# Controller-Modul_1.net
KiCad netlist of a schematic drawn in EAGLE
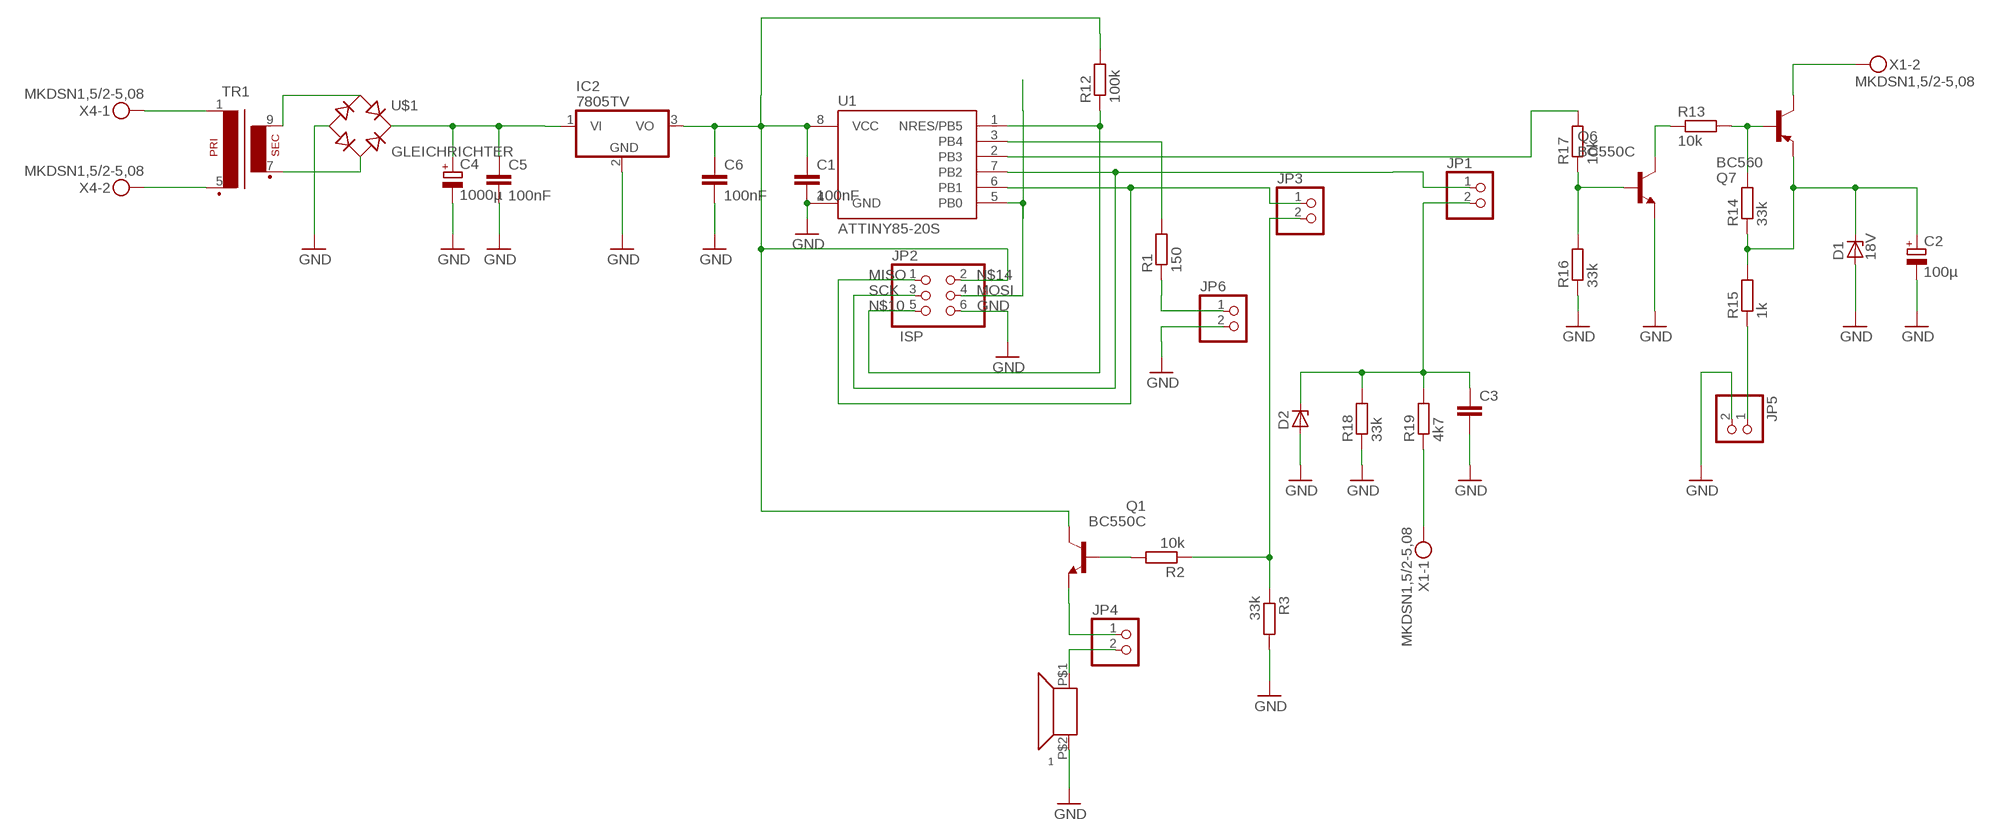
[diagram p0: schematic, sheet 1]

(export (version "E")
  (design (tool "Eeschema 10.0.6"))
  (components
    (comp (ref "1")
      (value "SUMMER4")
      (footprint "eagle-import:PIEZO-INDIKATOR-KPMG")
      (libsource (lib "eagle-import") (part "SUMMER4"))
    )
    (comp (ref "C1")
      (value "100nF")
      (footprint "eagle-import:C0805")
      (libsource (lib "eagle-import") (part "C-EUC0805"))
    )
    (comp (ref "C2")
      (value "100µ")
      (footprint "eagle-import:E2,5-7")
      (libsource (lib "eagle-import") (part "resistor_CPOL-EUE2.5-7"))
    )
    (comp (ref "C3")
      (value "C-EUC0603K")
      (footprint "eagle-import:C0603K")
      (libsource (lib "eagle-import") (part "C-EUC0603K"))
    )
    (comp (ref "C4")
      (value "1000µ")
      (footprint "eagle-import:E3,5-8")
      (libsource (lib "eagle-import") (part "CPOL-EUE3.5-8"))
    )
    (comp (ref "C5")
      (value "100nF")
      (footprint "eagle-import:C0805")
      (libsource (lib "eagle-import") (part "C-EUC0805"))
    )
    (comp (ref "C6")
      (value "100nF")
      (footprint "eagle-import:C0805")
      (libsource (lib "eagle-import") (part "C-EUC0805"))
    )
    (comp (ref "D1")
      (value "18V")
      (footprint "eagle-import:SOD80C")
      (libsource (lib "eagle-import") (part "ZENER-DIODESOD80C"))
    )
    (comp (ref "D2")
      (value "ZENER-DIODESOT23")
      (footprint "eagle-import:SOT23")
      (libsource (lib "eagle-import") (part "ZENER-DIODESOT23"))
    )
    (comp (ref "IC2")
      (value "7805TV")
      (footprint "eagle-import:TO220V")
      (libsource (lib "eagle-import") (part "78TV05"))
    )
    (comp (ref "JP1")
      (value "PINHD-1X2")
      (footprint "eagle-import:1X02")
      (libsource (lib "eagle-import") (part "PINHD-1X2"))
    )
    (comp (ref "JP2")
      (value "PINHD-2X3")
      (footprint "eagle-import:2X03")
      (libsource (lib "eagle-import") (part "PINHD-2X3"))
    )
    (comp (ref "JP3")
      (value "PINHD-1X2")
      (footprint "eagle-import:1X02")
      (libsource (lib "eagle-import") (part "PINHD-1X2"))
    )
    (comp (ref "JP4")
      (value "PINHD-1X2")
      (footprint "eagle-import:1X02")
      (libsource (lib "eagle-import") (part "PINHD-1X2"))
    )
    (comp (ref "JP5")
      (value "PINHD-1X2")
      (footprint "eagle-import:1X02")
      (libsource (lib "eagle-import") (part "PINHD-1X2"))
    )
    (comp (ref "JP6")
      (value "PINHD-1X2")
      (footprint "eagle-import:1X02")
      (libsource (lib "eagle-import") (part "PINHD-1X2"))
    )
    (comp (ref "Q1")
      (value "BC550C")
      (footprint "eagle-import:TO92-EBC")
      (libsource (lib "eagle-import") (part "BC550C"))
    )
    (comp (ref "Q6")
      (value "BC550C")
      (footprint "eagle-import:TO92-EBC")
      (libsource (lib "eagle-import") (part "BC550C"))
    )
    (comp (ref "Q7")
      (value "BC560")
      (footprint "eagle-import:TO92-EBC")
      (libsource (lib "eagle-import") (part "BC560"))
    )
    (comp (ref "R1")
      (value "150")
      (footprint "eagle-import:R1206")
      (libsource (lib "eagle-import") (part "R-EU_R1206"))
    )
    (comp (ref "R2")
      (value "10k")
      (footprint "eagle-import:R1206")
      (libsource (lib "eagle-import") (part "resistor_R-EU_R1206"))
    )
    (comp (ref "R3")
      (value "33k")
      (footprint "eagle-import:R1206")
      (libsource (lib "eagle-import") (part "resistor_R-EU_R1206"))
    )
    (comp (ref "R12")
      (value "100k")
      (footprint "eagle-import:R1206")
      (libsource (lib "eagle-import") (part "R-EU_R1206"))
    )
    (comp (ref "R13")
      (value "10k")
      (footprint "eagle-import:R1206")
      (libsource (lib "eagle-import") (part "resistor_R-EU_R1206"))
    )
    (comp (ref "R14")
      (value "33k")
      (footprint "eagle-import:R1206")
      (libsource (lib "eagle-import") (part "resistor_R-EU_R1206"))
    )
    (comp (ref "R15")
      (value "1k")
      (footprint "eagle-import:R1206")
      (libsource (lib "eagle-import") (part "resistor_R-EU_R1206"))
    )
    (comp (ref "R16")
      (value "33k")
      (footprint "eagle-import:R1206")
      (libsource (lib "eagle-import") (part "resistor_R-EU_R1206"))
    )
    (comp (ref "R17")
      (value "10k")
      (footprint "eagle-import:R1206")
      (libsource (lib "eagle-import") (part "resistor_R-EU_R1206"))
    )
    (comp (ref "R18")
      (value "33k")
      (footprint "eagle-import:R1206")
      (libsource (lib "eagle-import") (part "resistor_R-EU_R1206"))
    )
    (comp (ref "R19")
      (value "4k7")
      (footprint "eagle-import:R1206")
      (libsource (lib "eagle-import") (part "resistor_R-EU_R1206"))
    )
    (comp (ref "TR1")
      (value "EI38-1")
      (footprint "eagle-import:EI38-1")
      (libsource (lib "eagle-import") (part "EI38-1"))
    )
    (comp (ref "U$1")
      (value "GLEICHRICHTER")
      (footprint "eagle-import:KBPC1")
      (libsource (lib "eagle-import") (part "GLEICHRICHTER"))
    )
    (comp (ref "U1")
      (value "ATTINY85-20S")
      (footprint "eagle-import:SOIC8_EIAJ_208MIL")
      (libsource (lib "eagle-import") (part "ATTINY85S-20"))
    )
    (comp (ref "X1")
      (value "MKDSN1,5/2-5,08")
      (footprint "eagle-import:MKDSN1,5_2-5,08")
      (libsource (lib "eagle-import") (part "MKDSN1,5/2-5,08"))
    )
    (comp (ref "X4")
      (value "MKDSN1,5/2-5,08")
      (footprint "eagle-import:MKDSN1,5_2-5,08")
      (libsource (lib "eagle-import") (part "MKDSN1,5/2-5,08"))
    )
  )
  (nets
    (net (code "1") (name "/MISO") (class "Default")
      (node (ref "JP2") (pin "1") (pinfunction "1_1") (pintype "passive"))
      (node (ref "JP3") (pin "1") (pinfunction "1_1") (pintype "passive"))
      (node (ref "U1") (pin "6") (pinfunction "PB1_6") (pintype "bidirectional"))
    )
    (net (code "2") (name "/MOSI") (class "Default")
      (node (ref "JP2") (pin "4") (pinfunction "4_4") (pintype "passive"))
      (node (ref "U1") (pin "5") (pinfunction "PB0_5") (pintype "bidirectional"))
    )
    (net (code "3") (name "/N$10") (class "Default")
      (node (ref "JP2") (pin "5") (pinfunction "5_5") (pintype "passive"))
      (node (ref "R12") (pin "1") (pinfunction "1_1") (pintype "passive"))
      (node (ref "U1") (pin "1") (pinfunction "NRES/PB5_1") (pintype "bidirectional"))
    )
    (net (code "4") (name "/N$14") (class "Default")
      (node (ref "C1") (pin "1") (pinfunction "1_1") (pintype "passive"))
      (node (ref "C6") (pin "1") (pinfunction "1_1") (pintype "passive"))
      (node (ref "IC2") (pin "3") (pinfunction "VO_3") (pintype "passive"))
      (node (ref "JP2") (pin "2") (pinfunction "2_2") (pintype "passive"))
      (node (ref "Q1") (pin "C") (pinfunction "C_C") (pintype "passive"))
      (node (ref "R12") (pin "2") (pinfunction "2_2") (pintype "passive"))
      (node (ref "U1") (pin "8") (pinfunction "VCC_8") (pintype "power_in"))
    )
    (net (code "5") (name "/SCK") (class "Default")
      (node (ref "JP1") (pin "1") (pinfunction "1_1") (pintype "passive"))
      (node (ref "JP2") (pin "3") (pinfunction "3_3") (pintype "passive"))
      (node (ref "U1") (pin "7") (pinfunction "PB2_7") (pintype "bidirectional"))
    )
    (net (code "6") (name "GND") (class "Default")
      (node (ref "1") (pin "P$2") (pinfunction "+_P$2") (pintype "passive"))
      (node (ref "C1") (pin "2") (pinfunction "2_2") (pintype "passive"))
      (node (ref "C2") (pin "-") (pinfunction "-_-") (pintype "passive"))
      (node (ref "C3") (pin "2") (pinfunction "2_2") (pintype "passive"))
      (node (ref "C4") (pin "-") (pinfunction "-_-") (pintype "passive"))
      (node (ref "C5") (pin "2") (pinfunction "2_2") (pintype "passive"))
      (node (ref "C6") (pin "2") (pinfunction "2_2") (pintype "passive"))
      (node (ref "D1") (pin "A") (pinfunction "A_A") (pintype "passive"))
      (node (ref "D2") (pin "1") (pinfunction "A_1") (pintype "passive"))
      (node (ref "IC2") (pin "2") (pinfunction "GND_2") (pintype "passive"))
      (node (ref "JP2") (pin "6") (pinfunction "6_6") (pintype "passive"))
      (node (ref "JP5") (pin "2") (pinfunction "2_2") (pintype "passive"))
      (node (ref "JP6") (pin "2") (pinfunction "2_2") (pintype "passive"))
      (node (ref "Q6") (pin "E") (pinfunction "E_E") (pintype "passive"))
      (node (ref "R16") (pin "1") (pinfunction "1_1") (pintype "passive"))
      (node (ref "R18") (pin "1") (pinfunction "1_1") (pintype "passive"))
      (node (ref "R3") (pin "2") (pinfunction "2_2") (pintype "passive"))
      (node (ref "U$1") (pin "-") (pinfunction "-_-") (pintype "passive"))
      (node (ref "U1") (pin "4") (pinfunction "GND_4") (pintype "power_in"))
    )
    (net (code "7") (name "Net-(1--)") (class "Default")
      (node (ref "1") (pin "P$1") (pinfunction "-_P$1") (pintype "passive"))
      (node (ref "JP4") (pin "2") (pinfunction "2_2") (pintype "passive"))
    )
    (net (code "8") (name "Net-(C2-Pad+)") (class "Default")
      (node (ref "C2") (pin "+") (pinfunction "+_+") (pintype "passive"))
      (node (ref "D1") (pin "C") (pinfunction "C_C") (pintype "passive"))
      (node (ref "Q7") (pin "E") (pinfunction "E_E") (pintype "passive"))
      (node (ref "R14") (pin "1") (pinfunction "1_1") (pintype "passive"))
      (node (ref "R15") (pin "2") (pinfunction "2_2") (pintype "passive"))
    )
    (net (code "9") (name "Net-(D2-C)") (class "Default")
      (node (ref "C3") (pin "1") (pinfunction "1_1") (pintype "passive"))
      (node (ref "D2") (pin "3") (pinfunction "C_3") (pintype "passive"))
      (node (ref "JP1") (pin "2") (pinfunction "2_2") (pintype "passive"))
      (node (ref "R18") (pin "2") (pinfunction "2_2") (pintype "passive"))
      (node (ref "R19") (pin "2") (pinfunction "2_2") (pintype "passive"))
    )
    (net (code "10") (name "Net-(IC2-VI)") (class "Default")
      (node (ref "C4") (pin "+") (pinfunction "+_+") (pintype "passive"))
      (node (ref "C5") (pin "1") (pinfunction "1_1") (pintype "passive"))
      (node (ref "IC2") (pin "1") (pinfunction "VI_1") (pintype "input"))
      (node (ref "U$1") (pin "+") (pinfunction "+_+") (pintype "passive"))
    )
    (net (code "11") (name "Net-(JP3-Pad2)") (class "Default")
      (node (ref "JP3") (pin "2") (pinfunction "2_2") (pintype "passive"))
      (node (ref "R2") (pin "1") (pinfunction "1_1") (pintype "passive"))
      (node (ref "R3") (pin "1") (pinfunction "1_1") (pintype "passive"))
    )
    (net (code "12") (name "Net-(JP4-Pad1)") (class "Default")
      (node (ref "JP4") (pin "1") (pinfunction "1_1") (pintype "passive"))
      (node (ref "Q1") (pin "E") (pinfunction "E_E") (pintype "passive"))
    )
    (net (code "13") (name "Net-(JP5-Pad1)") (class "Default")
      (node (ref "JP5") (pin "1") (pinfunction "1_1") (pintype "passive"))
      (node (ref "R15") (pin "1") (pinfunction "1_1") (pintype "passive"))
    )
    (net (code "14") (name "Net-(JP6-Pad1)") (class "Default")
      (node (ref "JP6") (pin "1") (pinfunction "1_1") (pintype "passive"))
      (node (ref "R1") (pin "1") (pinfunction "1_1") (pintype "passive"))
    )
    (net (code "15") (name "Net-(Q1-PadB)") (class "Default")
      (node (ref "Q1") (pin "B") (pinfunction "B_B") (pintype "passive"))
      (node (ref "R2") (pin "2") (pinfunction "2_2") (pintype "passive"))
    )
    (net (code "16") (name "Net-(Q6-PadB)") (class "Default")
      (node (ref "Q6") (pin "B") (pinfunction "B_B") (pintype "passive"))
      (node (ref "R16") (pin "2") (pinfunction "2_2") (pintype "passive"))
      (node (ref "R17") (pin "1") (pinfunction "1_1") (pintype "passive"))
    )
    (net (code "17") (name "Net-(Q6-PadC)") (class "Default")
      (node (ref "Q6") (pin "C") (pinfunction "C_C") (pintype "passive"))
      (node (ref "R13") (pin "1") (pinfunction "1_1") (pintype "passive"))
    )
    (net (code "18") (name "Net-(Q7-PadB)") (class "Default")
      (node (ref "Q7") (pin "B") (pinfunction "B_B") (pintype "passive"))
      (node (ref "R13") (pin "2") (pinfunction "2_2") (pintype "passive"))
      (node (ref "R14") (pin "2") (pinfunction "2_2") (pintype "passive"))
    )
    (net (code "19") (name "Net-(TR1-P1)") (class "Default")
      (node (ref "TR1") (pin "1") (pinfunction "P1_1") (pintype "passive"))
      (node (ref "X4") (pin "1") (pinfunction "KL_1") (pintype "passive"))
    )
    (net (code "20") (name "Net-(TR1-P2)") (class "Default")
      (node (ref "TR1") (pin "5") (pinfunction "P2_5") (pintype "passive"))
      (node (ref "X4") (pin "2") (pinfunction "KL_2") (pintype "passive"))
    )
    (net (code "21") (name "Net-(TR1-S3)") (class "Default")
      (node (ref "TR1") (pin "7") (pinfunction "S3_7") (pintype "passive"))
      (node (ref "U$1") (pin "AC2") (pinfunction "AC2_AC2") (pintype "passive"))
    )
    (net (code "22") (name "Net-(TR1-S4)") (class "Default")
      (node (ref "TR1") (pin "9") (pinfunction "S4_9") (pintype "passive"))
      (node (ref "U$1") (pin "AC1") (pinfunction "AC1_AC1") (pintype "passive"))
    )
    (net (code "23") (name "Net-(U1-PB3)") (class "Default")
      (node (ref "R17") (pin "2") (pinfunction "2_2") (pintype "passive"))
      (node (ref "U1") (pin "2") (pinfunction "PB3_2") (pintype "bidirectional"))
    )
    (net (code "24") (name "Net-(U1-PB4)") (class "Default")
      (node (ref "R1") (pin "2") (pinfunction "2_2") (pintype "passive"))
      (node (ref "U1") (pin "3") (pinfunction "PB4_3") (pintype "bidirectional"))
    )
    (net (code "25") (name "Net-(X1A-KL)") (class "Default")
      (node (ref "R19") (pin "1") (pinfunction "1_1") (pintype "passive"))
      (node (ref "X1") (pin "1") (pinfunction "KL_1") (pintype "passive"))
    )
    (net (code "26") (name "Net-(X1B-KL)") (class "Default")
      (node (ref "Q7") (pin "C") (pinfunction "C_C") (pintype "passive"))
      (node (ref "X1") (pin "2") (pinfunction "KL_2") (pintype "passive"))
    )
  )
)
